# USB2Serial-CH340G-v1_0.net
KiCad netlist of a schematic drawn in EAGLE
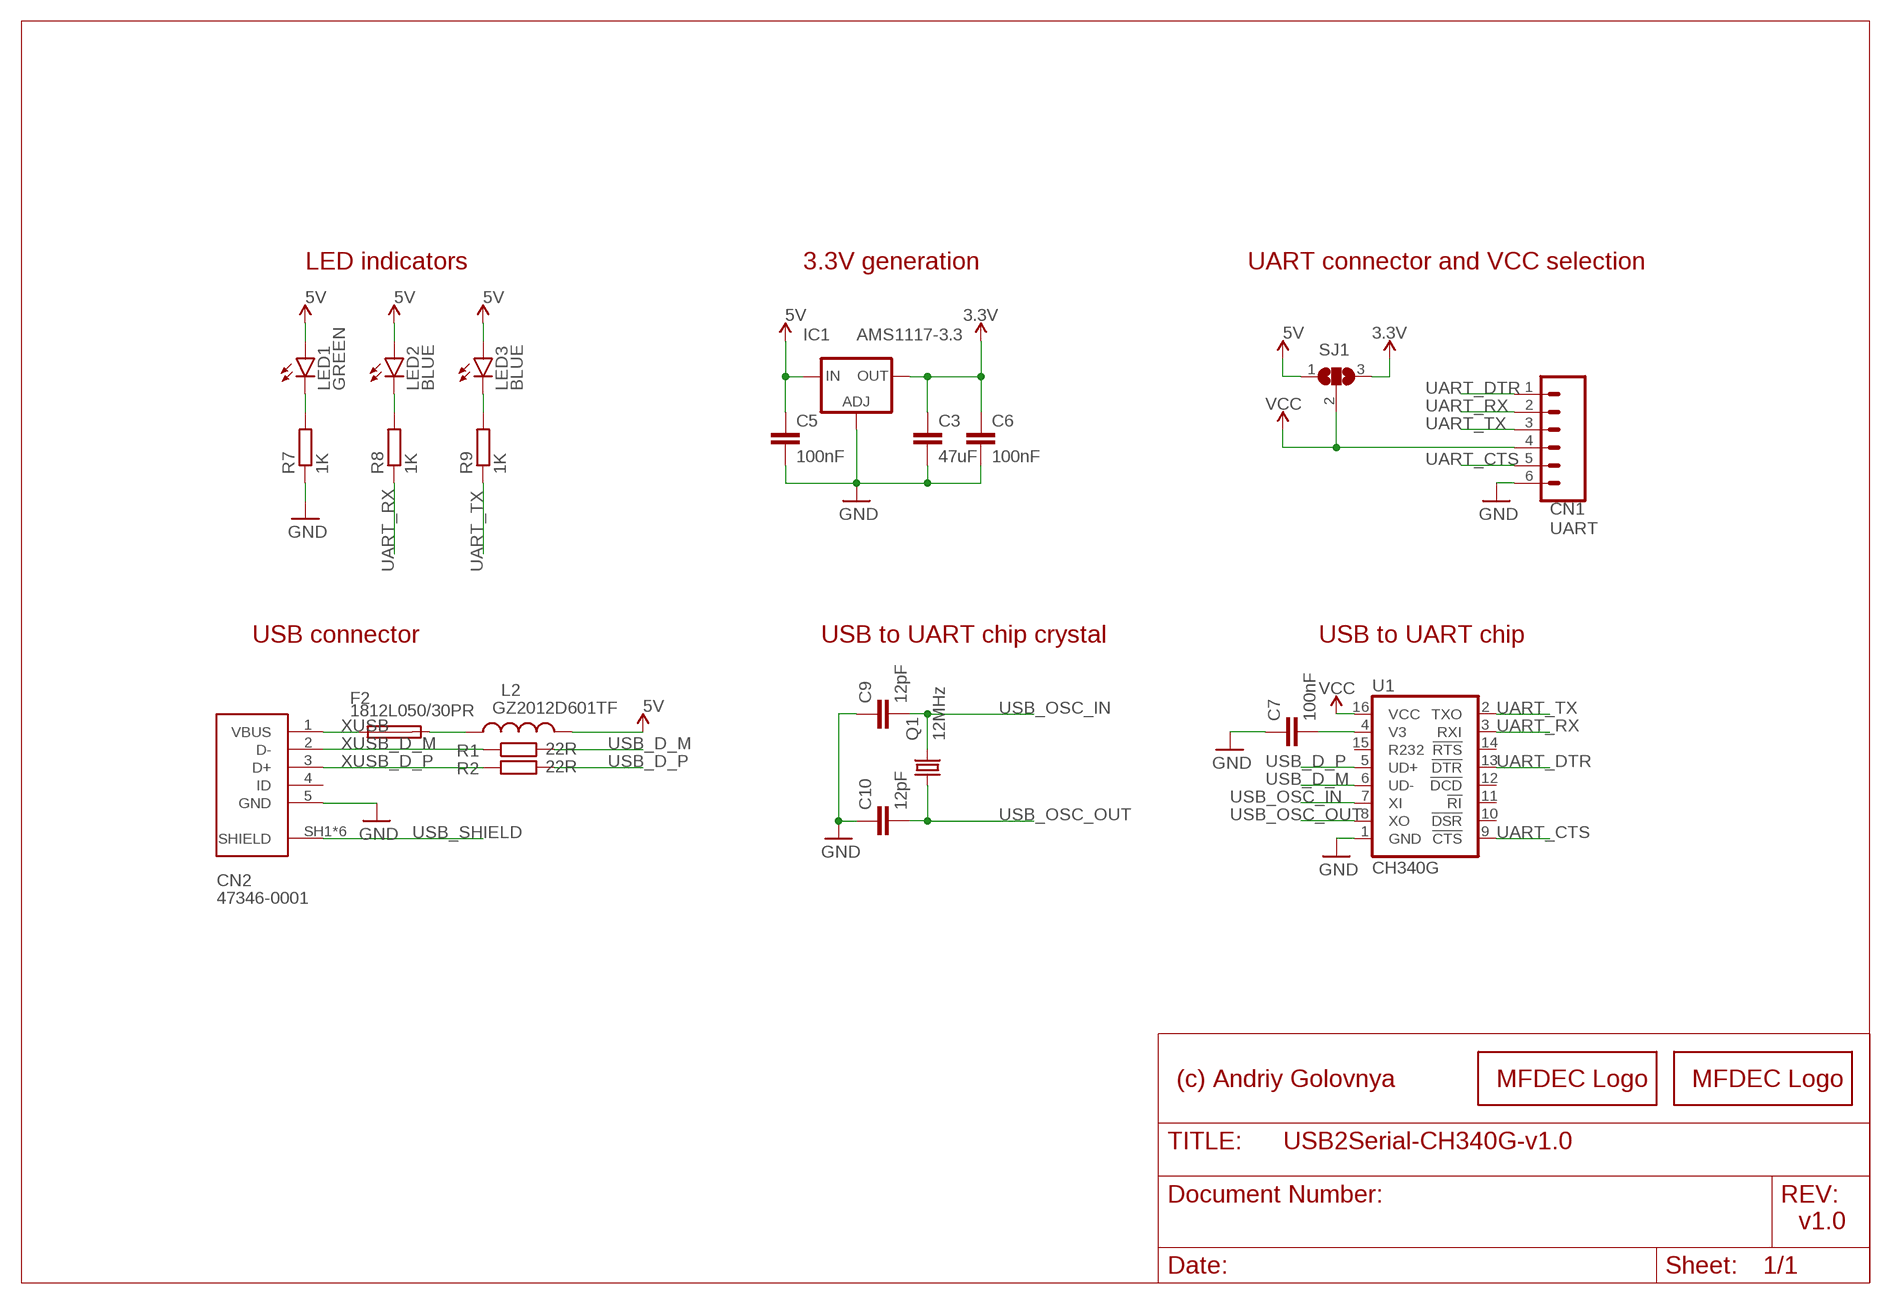
[diagram p0: schematic, sheet 1]

(export (version "E")
  (design (tool "Eeschema 10.0.6"))
  (components
    (comp (ref "C3")
      (value "47uF")
      (footprint "eagle-import:C0805")
      (libsource (lib "eagle-import") (part "C-EUC0805"))
    )
    (comp (ref "C5")
      (value "100nF")
      (footprint "eagle-import:C0402")
      (libsource (lib "eagle-import") (part "C-EUC0402"))
    )
    (comp (ref "C6")
      (value "100nF")
      (footprint "eagle-import:C0402")
      (libsource (lib "eagle-import") (part "C-EUC0402"))
    )
    (comp (ref "C7")
      (value "100nF")
      (footprint "eagle-import:C0402")
      (libsource (lib "eagle-import") (part "C-EUC0402"))
    )
    (comp (ref "C9")
      (value "12pF")
      (footprint "eagle-import:C0402")
      (libsource (lib "eagle-import") (part "C-EUC0402"))
    )
    (comp (ref "C10")
      (value "12pF")
      (footprint "eagle-import:C0402")
      (libsource (lib "eagle-import") (part "C-EUC0402"))
    )
    (comp (ref "CN1")
      (value "UART")
      (footprint "eagle-import:1X06_NO_SILK")
      (libsource (lib "eagle-import") (part "CONN_06NO_SILK_FEMALE_PTH"))
    )
    (comp (ref "CN2")
      (value "47346-0001")
      (footprint "eagle-import:MOLEX_47346-0001")
      (fields (field (name "MANUFACTURER") "Molex"))
      (libsource (lib "eagle-import") (part "47346-0001"))
    )
    (comp (ref "F2")
      (value "1812L050/30PR")
      (footprint "eagle-import:MF-SMDF050")
      (libsource (lib "eagle-import") (part "MF-SMDF050"))
    )
    (comp (ref "IC1")
      (value "AMS1117-3.3")
      (footprint "eagle-import:SOT223")
      (libsource (lib "eagle-import") (part "LD117A?S33TR"))
    )
    (comp (ref "L2")
      (value "GZ2012D601TF")
      (footprint "eagle-import:WE-CBA_0805(W=4)")
      (libsource (lib "eagle-import") (part "WE-CBA_0805_HC_782853102"))
    )
    (comp (ref "LED1")
      (value "GREEN")
      (footprint "eagle-import:SML0603")
      (libsource (lib "eagle-import") (part "LEDSML0603"))
    )
    (comp (ref "LED2")
      (value "BLUE")
      (footprint "eagle-import:SML0603")
      (libsource (lib "eagle-import") (part "LEDSML0603"))
    )
    (comp (ref "LED3")
      (value "BLUE")
      (footprint "eagle-import:SML0603")
      (libsource (lib "eagle-import") (part "LEDSML0603"))
    )
    (comp (ref "LOGO1")
      (value "MFDECLOGO_L_20MM")
      (footprint "eagle-import:MFDEC_L_20MM")
      (libsource (lib "eagle-import") (part "MFDECLOGO_L_20MM"))
    )
    (comp (ref "LOGO2")
      (value "MFDECLOGO_SQ_10MM")
      (footprint "eagle-import:MFDEC_SQ_10MM")
      (libsource (lib "eagle-import") (part "MFDECLOGO_SQ_10MM"))
    )
    (comp (ref "Q1")
      (value "12MHz")
      (footprint "eagle-import:3.2X2.5_KX-7")
      (libsource (lib "eagle-import") (part "KX-7"))
    )
    (comp (ref "R1")
      (value "22R")
      (footprint "eagle-import:R0402")
      (libsource (lib "eagle-import") (part "R-EU_R0402"))
    )
    (comp (ref "R2")
      (value "22R")
      (footprint "eagle-import:R0402")
      (libsource (lib "eagle-import") (part "R-EU_R0402"))
    )
    (comp (ref "R7")
      (value "1K")
      (footprint "eagle-import:R0402")
      (libsource (lib "eagle-import") (part "R-EU_R0402"))
    )
    (comp (ref "R8")
      (value "1K")
      (footprint "eagle-import:R0402")
      (libsource (lib "eagle-import") (part "R-EU_R0402"))
    )
    (comp (ref "R9")
      (value "1K")
      (footprint "eagle-import:R0402")
      (libsource (lib "eagle-import") (part "R-EU_R0402"))
    )
    (comp (ref "SJ1")
      (value "SJ2FI")
      (footprint "eagle-import:SJ_2FI")
      (libsource (lib "eagle-import") (part "SJ2FI"))
    )
    (comp (ref "U1")
      (value "CH340G")
      (footprint "eagle-import:SO016")
      (libsource (lib "eagle-import") (part "CH340GSMD"))
    )
  )
  (nets
    (net (code "1") (name "/UART_CTS") (class "Default")
      (node (ref "CN1") (pin "5") (pinfunction "5_5") (pintype "passive"))
      (node (ref "U1") (pin "9") (pinfunction "~{CTS}_9") (pintype "bidirectional"))
    )
    (net (code "2") (name "/UART_DTR") (class "Default")
      (node (ref "CN1") (pin "1") (pinfunction "1_1") (pintype "passive"))
      (node (ref "U1") (pin "13") (pinfunction "~{DTR}_13") (pintype "bidirectional"))
    )
    (net (code "3") (name "/UART_RX") (class "Default")
      (node (ref "CN1") (pin "2") (pinfunction "2_2") (pintype "passive"))
      (node (ref "R8") (pin "1") (pinfunction "1_1") (pintype "passive"))
      (node (ref "U1") (pin "3") (pinfunction "RXI_3") (pintype "bidirectional"))
    )
    (net (code "4") (name "/UART_TX") (class "Default")
      (node (ref "CN1") (pin "3") (pinfunction "3_3") (pintype "passive"))
      (node (ref "R9") (pin "1") (pinfunction "1_1") (pintype "passive"))
      (node (ref "U1") (pin "2") (pinfunction "TXO_2") (pintype "bidirectional"))
    )
    (net (code "5") (name "/USB_D_M") (class "Default")
      (node (ref "R1") (pin "2") (pinfunction "2_2") (pintype "passive"))
      (node (ref "U1") (pin "6") (pinfunction "UD-_6") (pintype "bidirectional"))
    )
    (net (code "6") (name "/USB_D_P") (class "Default")
      (node (ref "R2") (pin "2") (pinfunction "2_2") (pintype "passive"))
      (node (ref "U1") (pin "5") (pinfunction "UD+_5") (pintype "bidirectional"))
    )
    (net (code "7") (name "/USB_OSC_IN") (class "Default")
      (node (ref "C9") (pin "2") (pinfunction "2_2") (pintype "passive"))
      (node (ref "Q1") (pin "3") (pinfunction "2_3") (pintype "passive"))
      (node (ref "U1") (pin "7") (pinfunction "XI_7") (pintype "bidirectional"))
    )
    (net (code "8") (name "/USB_OSC_OUT") (class "Default")
      (node (ref "C10") (pin "2") (pinfunction "2_2") (pintype "passive"))
      (node (ref "Q1") (pin "1") (pinfunction "1_1") (pintype "passive"))
      (node (ref "U1") (pin "8") (pinfunction "XO_8") (pintype "bidirectional"))
    )
    (net (code "9") (name "/USB_SHIELD") (class "Default")
      (node (ref "CN2") (pin "SH1") (pinfunction "SHIELD_SH1") (pintype "passive"))
      (node (ref "CN2") (pin "SH2") (pinfunction "SHIELD_SH2") (pintype "passive"))
      (node (ref "CN2") (pin "SH3") (pinfunction "SHIELD_SH3") (pintype "passive"))
      (node (ref "CN2") (pin "SH4") (pinfunction "SHIELD_SH4") (pintype "passive"))
      (node (ref "CN2") (pin "SH5") (pinfunction "SHIELD_SH5") (pintype "passive"))
      (node (ref "CN2") (pin "SH6") (pinfunction "SHIELD_SH6") (pintype "passive"))
    )
    (net (code "10") (name "/XUSB") (class "Default")
      (node (ref "CN2") (pin "1") (pinfunction "VBUS_1") (pintype "power_in"))
      (node (ref "F2") (pin "1") (pinfunction "1_1") (pintype "passive"))
    )
    (net (code "11") (name "/XUSB_D_M") (class "Default")
      (node (ref "CN2") (pin "2") (pinfunction "D-_2") (pintype "bidirectional"))
      (node (ref "R1") (pin "1") (pinfunction "1_1") (pintype "passive"))
    )
    (net (code "12") (name "/XUSB_D_P") (class "Default")
      (node (ref "CN2") (pin "3") (pinfunction "D+_3") (pintype "bidirectional"))
      (node (ref "R2") (pin "1") (pinfunction "1_1") (pintype "passive"))
    )
    (net (code "13") (name "3.3V") (class "Default")
      (node (ref "C3") (pin "1") (pinfunction "1_1") (pintype "passive"))
      (node (ref "C6") (pin "1") (pinfunction "1_1") (pintype "passive"))
      (node (ref "IC1") (pin "4") (pinfunction "OUT_4") (pintype "passive"))
      (node (ref "SJ1") (pin "3") (pinfunction "3_3") (pintype "passive"))
    )
    (net (code "14") (name "5V") (class "Default")
      (node (ref "C5") (pin "1") (pinfunction "1_1") (pintype "passive"))
      (node (ref "IC1") (pin "3") (pinfunction "IN_3") (pintype "input"))
      (node (ref "L2") (pin "2") (pinfunction "2_2") (pintype "passive"))
      (node (ref "LED1") (pin "A") (pinfunction "A_A") (pintype "passive"))
      (node (ref "LED2") (pin "A") (pinfunction "A_A") (pintype "passive"))
      (node (ref "LED3") (pin "A") (pinfunction "A_A") (pintype "passive"))
      (node (ref "SJ1") (pin "1") (pinfunction "1_1") (pintype "passive"))
    )
    (net (code "15") (name "GND") (class "Default")
      (node (ref "C10") (pin "1") (pinfunction "1_1") (pintype "passive"))
      (node (ref "C3") (pin "2") (pinfunction "2_2") (pintype "passive"))
      (node (ref "C5") (pin "2") (pinfunction "2_2") (pintype "passive"))
      (node (ref "C6") (pin "2") (pinfunction "2_2") (pintype "passive"))
      (node (ref "C7") (pin "1") (pinfunction "1_1") (pintype "passive"))
      (node (ref "C9") (pin "1") (pinfunction "1_1") (pintype "passive"))
      (node (ref "CN1") (pin "6") (pinfunction "6_6") (pintype "passive"))
      (node (ref "CN2") (pin "5") (pinfunction "GND_5") (pintype "power_in"))
      (node (ref "IC1") (pin "1") (pinfunction "ADJ_1") (pintype "input"))
      (node (ref "R7") (pin "1") (pinfunction "1_1") (pintype "passive"))
      (node (ref "U1") (pin "1") (pinfunction "GND_1") (pintype "bidirectional"))
    )
    (net (code "16") (name "Net-(F2-Pad2)") (class "Default")
      (node (ref "F2") (pin "2") (pinfunction "2_2") (pintype "passive"))
      (node (ref "L2") (pin "1") (pinfunction "1_1") (pintype "passive"))
    )
    (net (code "17") (name "Net-(LED1-PadC)") (class "Default")
      (node (ref "LED1") (pin "C") (pinfunction "C_C") (pintype "passive"))
      (node (ref "R7") (pin "2") (pinfunction "2_2") (pintype "passive"))
    )
    (net (code "18") (name "Net-(LED2-PadC)") (class "Default")
      (node (ref "LED2") (pin "C") (pinfunction "C_C") (pintype "passive"))
      (node (ref "R8") (pin "2") (pinfunction "2_2") (pintype "passive"))
    )
    (net (code "19") (name "Net-(LED3-PadC)") (class "Default")
      (node (ref "LED3") (pin "C") (pinfunction "C_C") (pintype "passive"))
      (node (ref "R9") (pin "2") (pinfunction "2_2") (pintype "passive"))
    )
    (net (code "20") (name "Net-(U1-V3)") (class "Default")
      (node (ref "C7") (pin "2") (pinfunction "2_2") (pintype "passive"))
      (node (ref "U1") (pin "4") (pinfunction "V3_4") (pintype "bidirectional"))
    )
    (net (code "21") (name "VCC") (class "Default")
      (node (ref "CN1") (pin "4") (pinfunction "4_4") (pintype "passive"))
      (node (ref "SJ1") (pin "2") (pinfunction "2_2") (pintype "passive"))
      (node (ref "U1") (pin "16") (pinfunction "VCC_16") (pintype "bidirectional"))
    )
    (net (code "22") (name "unconnected-(CN2-ID-Pad4)") (class "Default")
      (node (ref "CN2") (pin "4") (pinfunction "ID_4") (pintype "passive"))
    )
    (net (code "23") (name "unconnected-(U1-R232-Pad15)") (class "Default")
      (node (ref "U1") (pin "15") (pinfunction "R232_15") (pintype "bidirectional"))
    )
    (net (code "24") (name "unconnected-(U1-~{DCD}-Pad12)") (class "Default")
      (node (ref "U1") (pin "12") (pinfunction "~{DCD}_12") (pintype "bidirectional"))
    )
    (net (code "25") (name "unconnected-(U1-~{DSR}-Pad10)") (class "Default")
      (node (ref "U1") (pin "10") (pinfunction "~{DSR}_10") (pintype "bidirectional"))
    )
    (net (code "26") (name "unconnected-(U1-~{RI}-Pad11)") (class "Default")
      (node (ref "U1") (pin "11") (pinfunction "~{RI}_11") (pintype "bidirectional"))
    )
    (net (code "27") (name "unconnected-(U1-~{RTS}-Pad14)") (class "Default")
      (node (ref "U1") (pin "14") (pinfunction "~{RTS}_14") (pintype "bidirectional"))
    )
  )
)
